# apple-idun.net
KiCad netlist of a schematic drawn in EAGLE
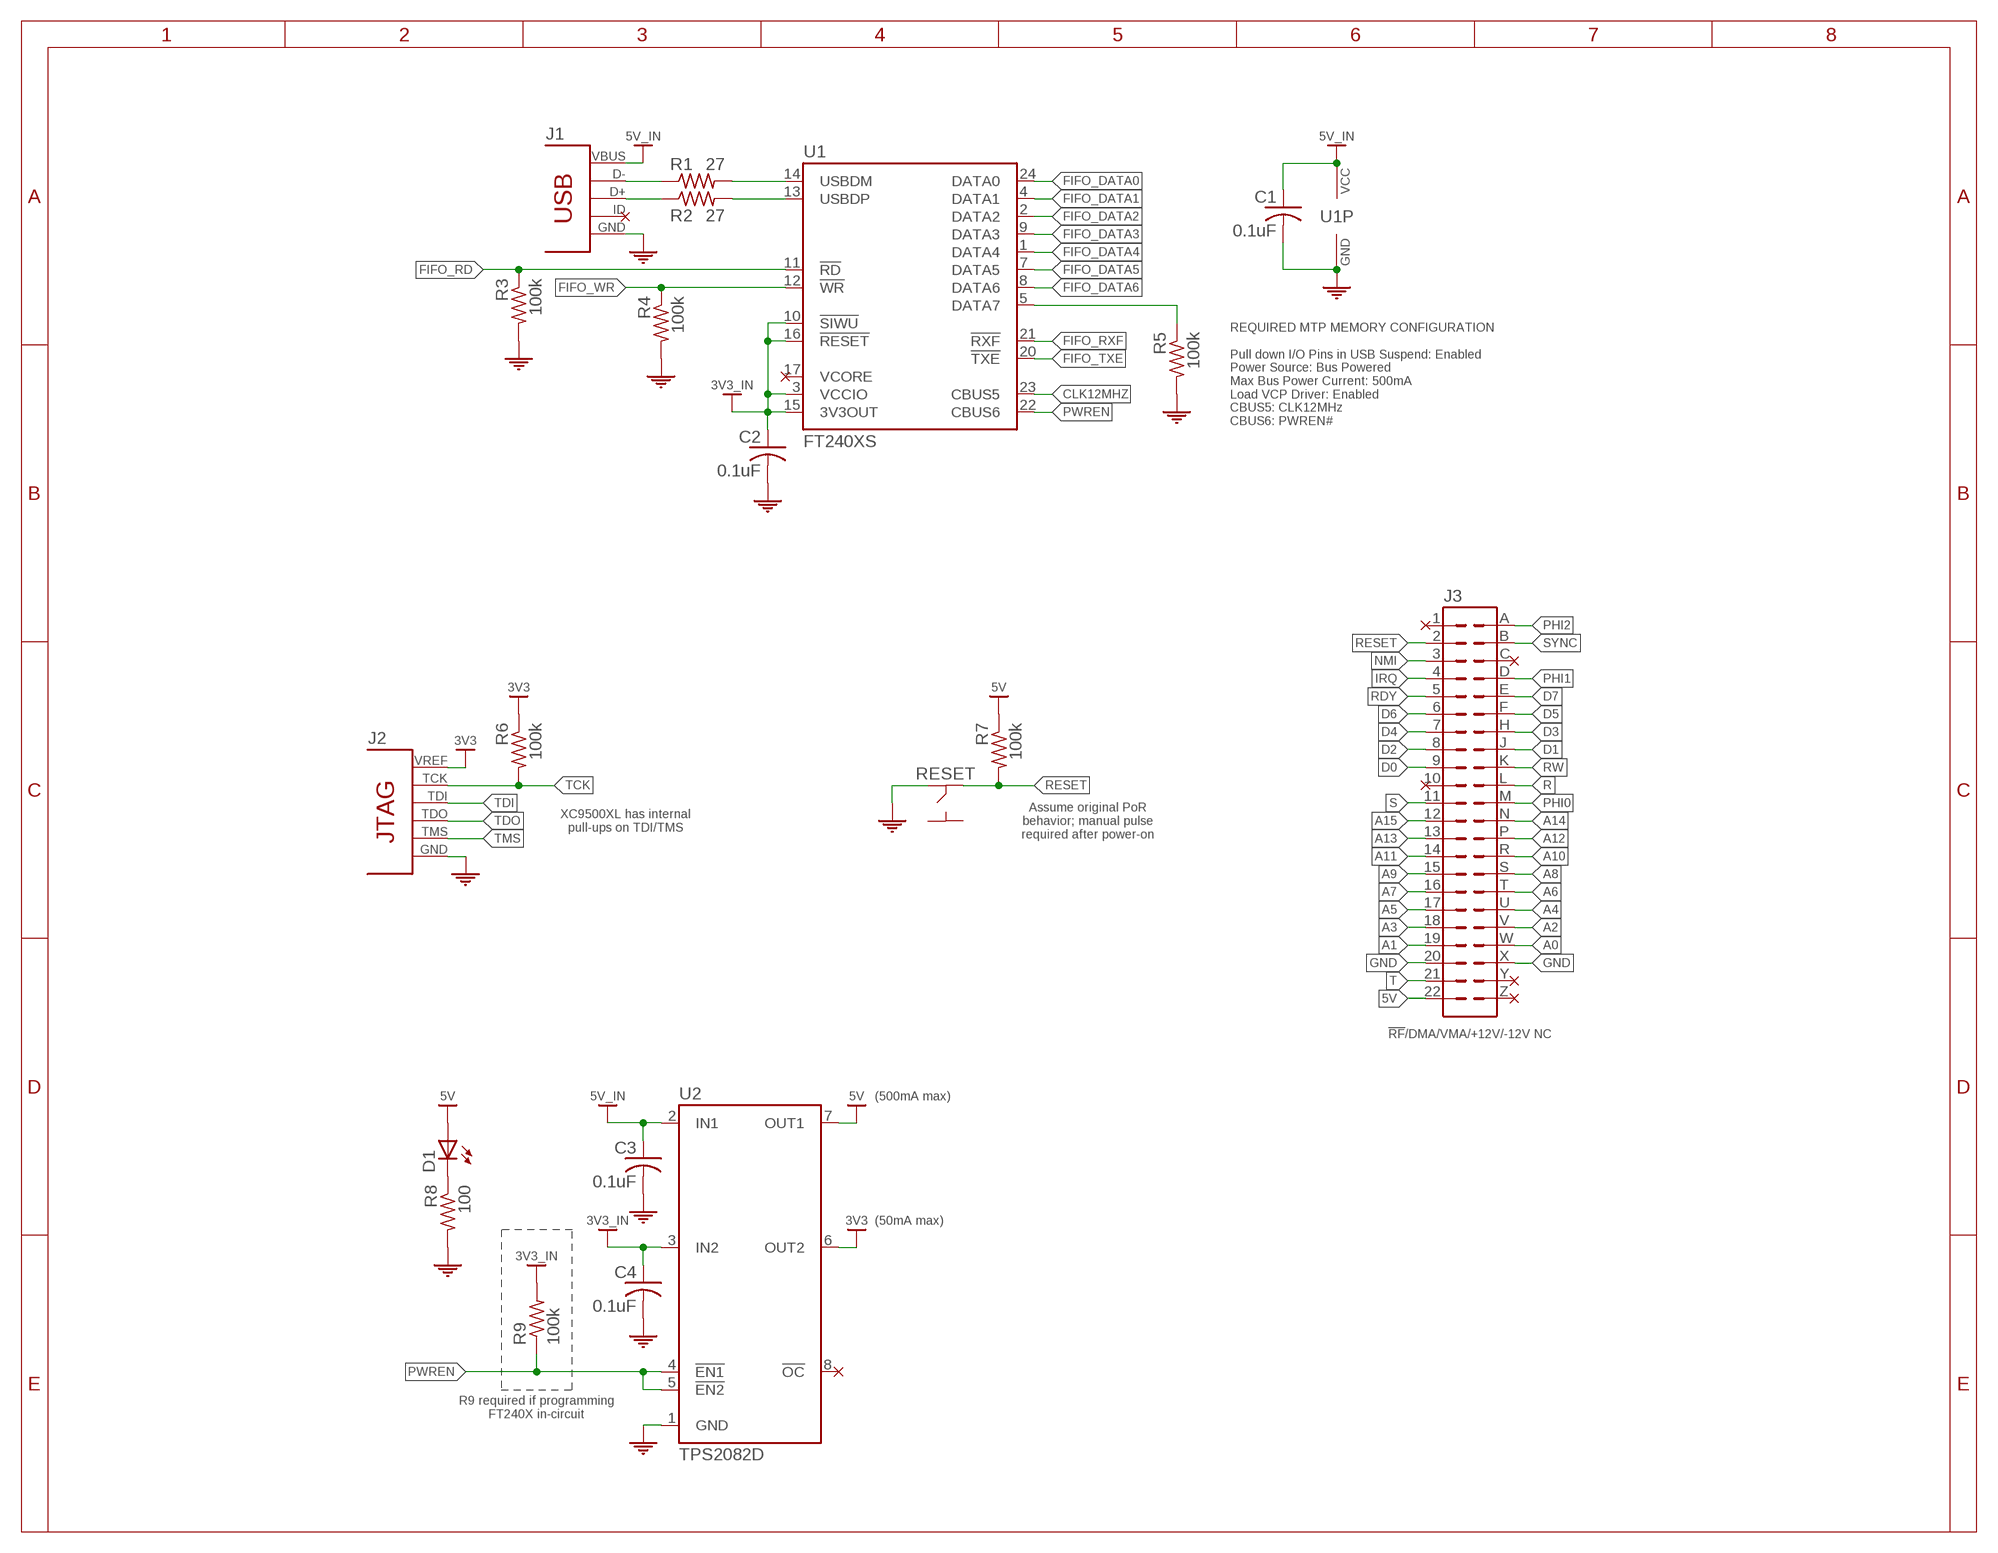
[diagram p0: schematic, sheet 1]
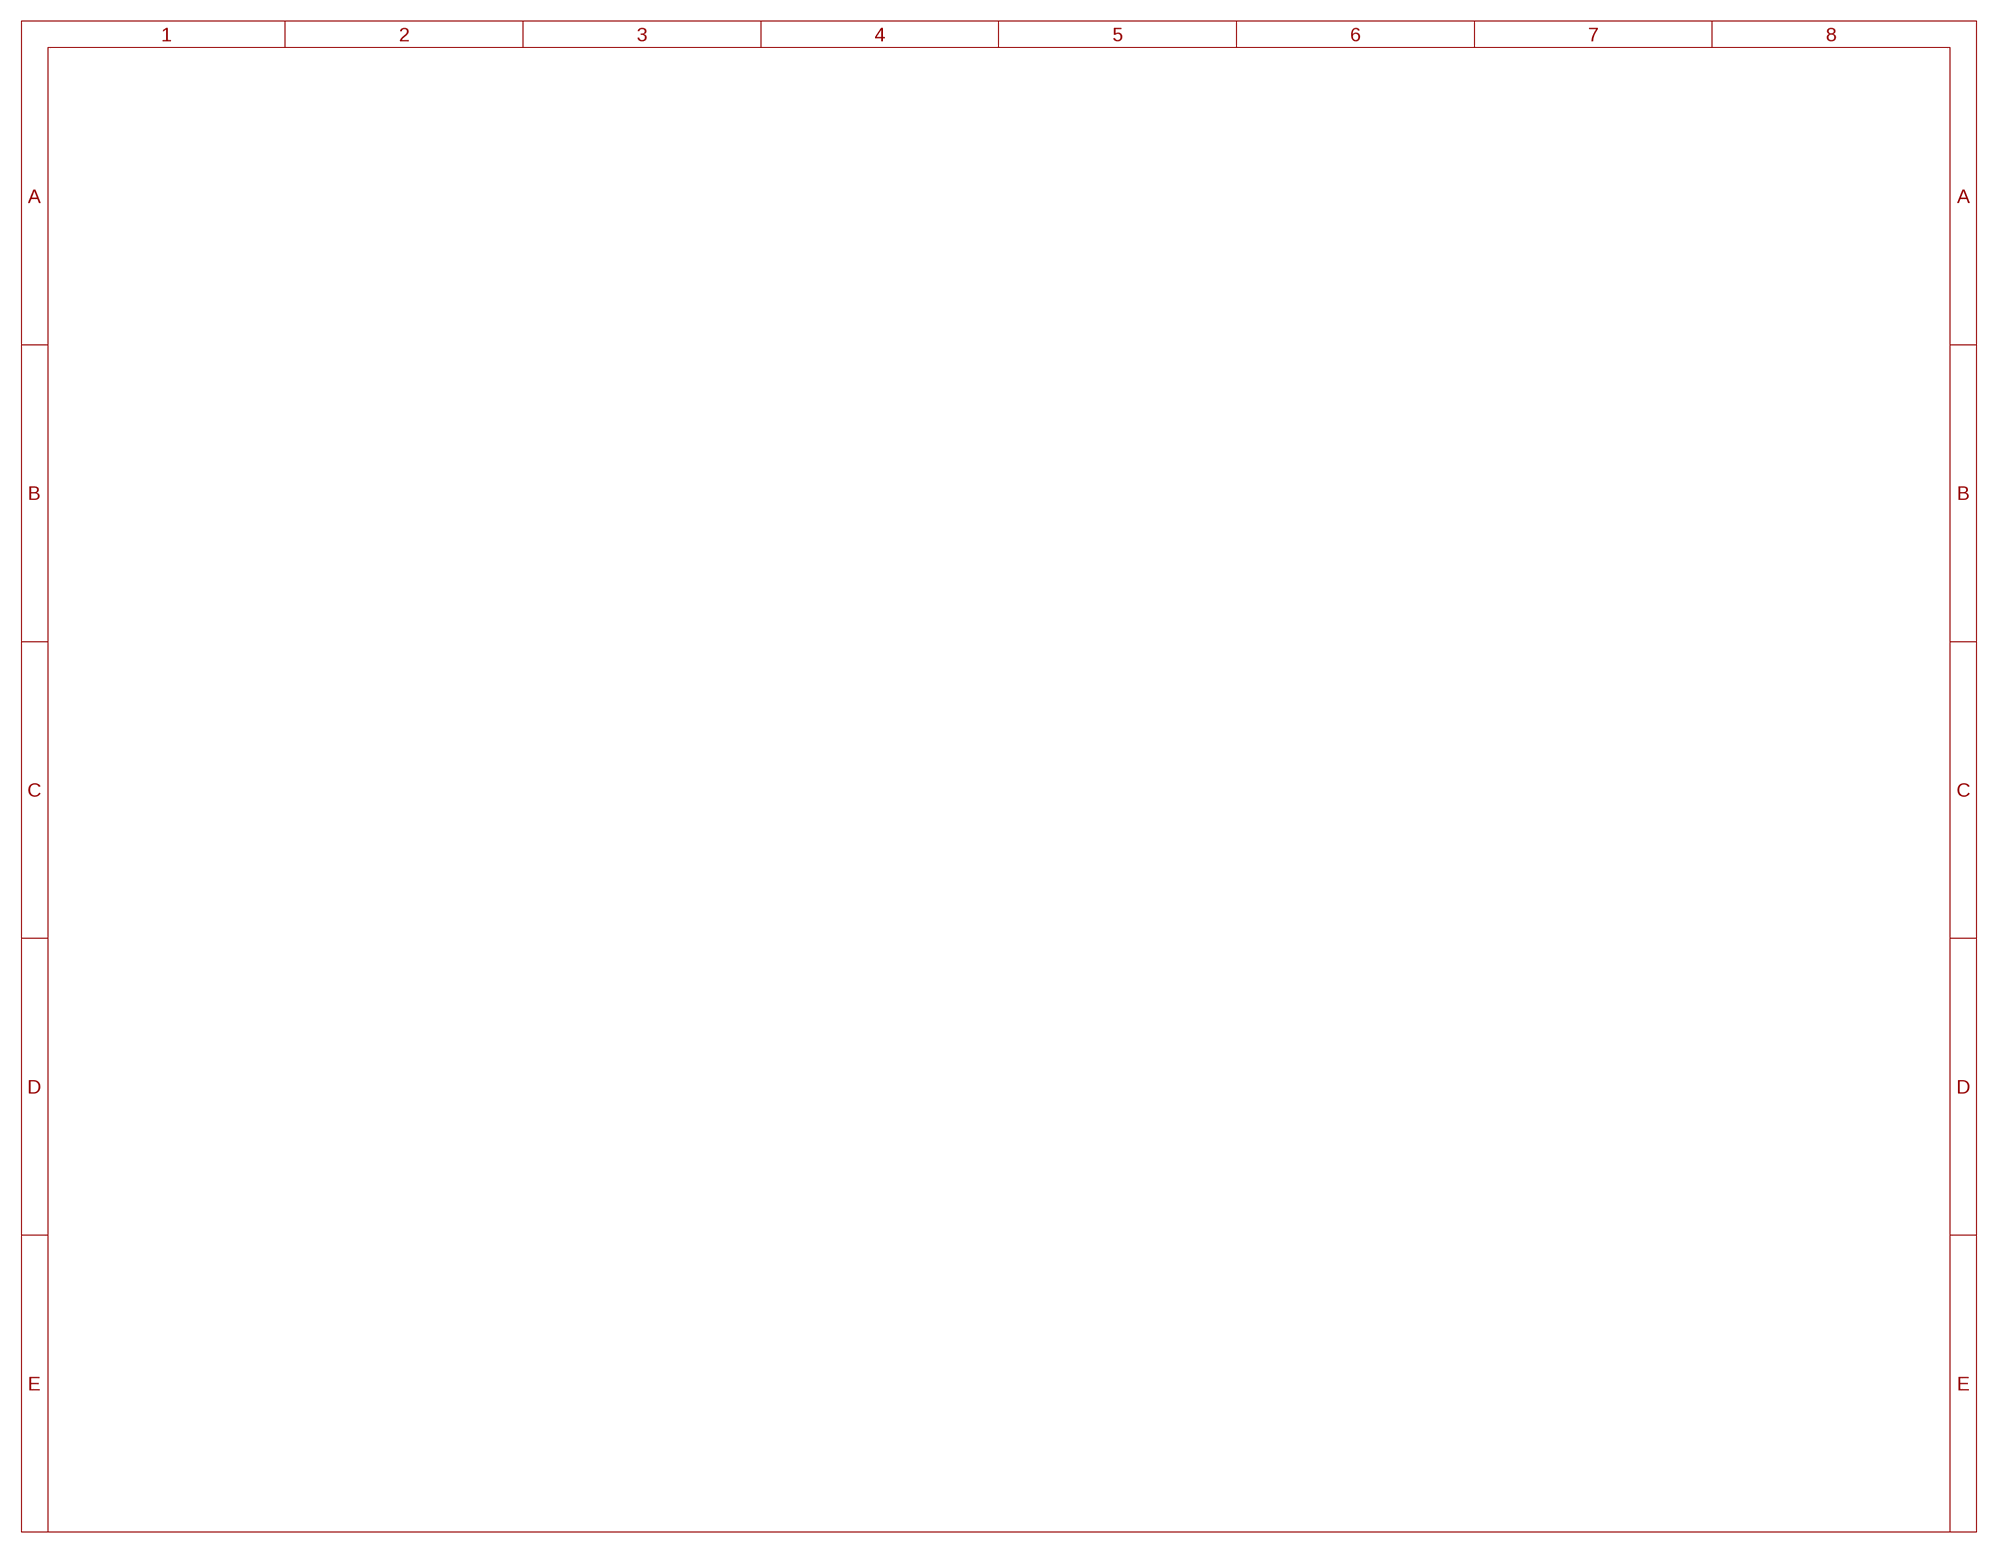
[diagram p1: schematic, sheet 2]

(export (version "E")
  (design (tool "Eeschema 10.0.6"))
  (components
    (comp (ref "C1")
      (value "0.1uF")
      (footprint "eagle-import:C0805")
      (libsource (lib "eagle-import") (part "C-USC0805"))
    )
    (comp (ref "C2")
      (value "0.1uF")
      (footprint "eagle-import:C0805")
      (libsource (lib "eagle-import") (part "C-USC0805"))
    )
    (comp (ref "C3")
      (value "0.1uF")
      (footprint "eagle-import:C0805")
      (libsource (lib "eagle-import") (part "C-USC0805"))
    )
    (comp (ref "C4")
      (value "0.1uF")
      (footprint "eagle-import:C0805")
      (libsource (lib "eagle-import") (part "C-USC0805"))
    )
    (comp (ref "D1")
      (value "LEDCHIP-LED0805")
      (footprint "eagle-import:CHIP-LED0805")
      (libsource (lib "eagle-import") (part "LEDCHIP-LED0805"))
    )
    (comp (ref "J1")
      (value "USBMICROB")
      (footprint "eagle-import:USBMICROB")
      (libsource (lib "eagle-import") (part "USBMICROB"))
    )
    (comp (ref "J2")
      (value "JTAG")
      (footprint "eagle-import:JTAG")
      (libsource (lib "eagle-import") (part "JTAG"))
    )
    (comp (ref "J3")
      (value "CON2X22")
      (footprint "eagle-import:CON2X22")
      (libsource (lib "eagle-import") (part "CON2X22"))
    )
    (comp (ref "R1")
      (value "27")
      (footprint "eagle-import:R0805")
      (libsource (lib "eagle-import") (part "R-US_R0805"))
    )
    (comp (ref "R2")
      (value "27")
      (footprint "eagle-import:R0805")
      (libsource (lib "eagle-import") (part "R-US_R0805"))
    )
    (comp (ref "R3")
      (value "100k")
      (footprint "eagle-import:R0805")
      (libsource (lib "eagle-import") (part "R-US_R0805"))
    )
    (comp (ref "R4")
      (value "100k")
      (footprint "eagle-import:R0805")
      (libsource (lib "eagle-import") (part "R-US_R0805"))
    )
    (comp (ref "R5")
      (value "100k")
      (footprint "eagle-import:R0805")
      (libsource (lib "eagle-import") (part "R-US_R0805"))
    )
    (comp (ref "R6")
      (value "100k")
      (footprint "eagle-import:R0805")
      (libsource (lib "eagle-import") (part "R-US_R0805"))
    )
    (comp (ref "R7")
      (value "100k")
      (footprint "eagle-import:R0805")
      (libsource (lib "eagle-import") (part "R-US_R0805"))
    )
    (comp (ref "R8")
      (value "100")
      (footprint "eagle-import:R0805")
      (libsource (lib "eagle-import") (part "R-US_R0805"))
    )
    (comp (ref "R9")
      (value "100k")
      (footprint "eagle-import:R0805")
      (libsource (lib "eagle-import") (part "R-US_R0805"))
    )
    (comp (ref "RESET")
      (value "TACTSW")
      (footprint "eagle-import:TACTSW")
      (libsource (lib "eagle-import") (part "TACTSW"))
    )
    (comp (ref "U1")
      (value "FT240XS")
      (footprint "eagle-import:SSOP24")
      (libsource (lib "eagle-import") (part "FT240XS"))
    )
    (comp (ref "U2")
      (value "TPS2082D")
      (footprint "eagle-import:SOIC8")
      (libsource (lib "eagle-import") (part "TPS2082D"))
    )
  )
  (nets
    (net (code "1") (name "3V3") (class "Default")
      (node (ref "J2") (pin "VREF") (pinfunction "VREF_VREF") (pintype "power_in"))
      (node (ref "R6") (pin "1") (pinfunction "1_1") (pintype "passive"))
      (node (ref "U2") (pin "6") (pinfunction "OUT2_6") (pintype "output"))
    )
    (net (code "2") (name "3V3_IN") (class "Default")
      (node (ref "C2") (pin "1") (pinfunction "1_1") (pintype "passive"))
      (node (ref "C4") (pin "1") (pinfunction "1_1") (pintype "passive"))
      (node (ref "R9") (pin "2") (pinfunction "2_2") (pintype "passive"))
      (node (ref "U1") (pin "10") (pinfunction "~{SIWU}_10") (pintype "input"))
      (node (ref "U1") (pin "15") (pinfunction "3V3OUT_15") (pintype "power_in"))
      (node (ref "U1") (pin "16") (pinfunction "~{RESET}_16") (pintype "input"))
      (node (ref "U1") (pin "3") (pinfunction "VCCIO_3") (pintype "power_in"))
      (node (ref "U2") (pin "3") (pinfunction "IN2_3") (pintype "input"))
    )
    (net (code "3") (name "5V") (class "Default")
      (node (ref "D1") (pin "A") (pinfunction "A_A") (pintype "passive"))
      (node (ref "J3") (pin "22") (pinfunction "22_22") (pintype "passive"))
      (node (ref "R7") (pin "1") (pinfunction "1_1") (pintype "passive"))
      (node (ref "U2") (pin "7") (pinfunction "OUT1_7") (pintype "output"))
    )
    (net (code "4") (name "5V_IN") (class "Default")
      (node (ref "C1") (pin "1") (pinfunction "1_1") (pintype "passive"))
      (node (ref "C3") (pin "1") (pinfunction "1_1") (pintype "passive"))
      (node (ref "J1") (pin "1") (pinfunction "1_1") (pintype "power_in"))
      (node (ref "U1") (pin "18") (pinfunction "VCC_18") (pintype "power_in"))
      (node (ref "U2") (pin "2") (pinfunction "IN1_2") (pintype "input"))
    )
    (net (code "5") (name "A0") (class "Default")
      (node (ref "J3") (pin "W") (pinfunction "W_W") (pintype "passive"))
    )
    (net (code "6") (name "A1") (class "Default")
      (node (ref "J3") (pin "19") (pinfunction "19_19") (pintype "passive"))
    )
    (net (code "7") (name "A2") (class "Default")
      (node (ref "J3") (pin "V") (pinfunction "V_V") (pintype "passive"))
    )
    (net (code "8") (name "A3") (class "Default")
      (node (ref "J3") (pin "18") (pinfunction "18_18") (pintype "passive"))
    )
    (net (code "9") (name "A4") (class "Default")
      (node (ref "J3") (pin "U") (pinfunction "U_U") (pintype "passive"))
    )
    (net (code "10") (name "A5") (class "Default")
      (node (ref "J3") (pin "17") (pinfunction "17_17") (pintype "passive"))
    )
    (net (code "11") (name "A6") (class "Default")
      (node (ref "J3") (pin "T") (pinfunction "T_T") (pintype "passive"))
    )
    (net (code "12") (name "A7") (class "Default")
      (node (ref "J3") (pin "16") (pinfunction "16_16") (pintype "passive"))
    )
    (net (code "13") (name "A8") (class "Default")
      (node (ref "J3") (pin "S") (pinfunction "S_S") (pintype "passive"))
    )
    (net (code "14") (name "A9") (class "Default")
      (node (ref "J3") (pin "15") (pinfunction "15_15") (pintype "passive"))
    )
    (net (code "15") (name "A10") (class "Default")
      (node (ref "J3") (pin "R") (pinfunction "R_R") (pintype "passive"))
    )
    (net (code "16") (name "A11") (class "Default")
      (node (ref "J3") (pin "14") (pinfunction "14_14") (pintype "passive"))
    )
    (net (code "17") (name "A12") (class "Default")
      (node (ref "J3") (pin "P") (pinfunction "P_P") (pintype "passive"))
    )
    (net (code "18") (name "A13") (class "Default")
      (node (ref "J3") (pin "13") (pinfunction "13_13") (pintype "passive"))
    )
    (net (code "19") (name "A14") (class "Default")
      (node (ref "J3") (pin "N") (pinfunction "N_N") (pintype "passive"))
    )
    (net (code "20") (name "A15") (class "Default")
      (node (ref "J3") (pin "12") (pinfunction "12_12") (pintype "passive"))
    )
    (net (code "21") (name "CLK12MHZ") (class "Default")
      (node (ref "U1") (pin "23") (pinfunction "CBUS5_23") (pintype "bidirectional"))
    )
    (net (code "22") (name "D0") (class "Default")
      (node (ref "J3") (pin "9") (pinfunction "9_9") (pintype "passive"))
    )
    (net (code "23") (name "D1") (class "Default")
      (node (ref "J3") (pin "J") (pinfunction "J_J") (pintype "passive"))
    )
    (net (code "24") (name "D2") (class "Default")
      (node (ref "J3") (pin "8") (pinfunction "8_8") (pintype "passive"))
    )
    (net (code "25") (name "D3") (class "Default")
      (node (ref "J3") (pin "H") (pinfunction "H_H") (pintype "passive"))
    )
    (net (code "26") (name "D4") (class "Default")
      (node (ref "J3") (pin "7") (pinfunction "7_7") (pintype "passive"))
    )
    (net (code "27") (name "D5") (class "Default")
      (node (ref "J3") (pin "F") (pinfunction "F_F") (pintype "passive"))
    )
    (net (code "28") (name "D6") (class "Default")
      (node (ref "J3") (pin "6") (pinfunction "6_6") (pintype "passive"))
    )
    (net (code "29") (name "D7") (class "Default")
      (node (ref "J3") (pin "E") (pinfunction "E_E") (pintype "passive"))
    )
    (net (code "30") (name "FIFO_DATA0") (class "Default")
      (node (ref "U1") (pin "24") (pinfunction "DATA0_24") (pintype "bidirectional"))
    )
    (net (code "31") (name "FIFO_DATA1") (class "Default")
      (node (ref "U1") (pin "4") (pinfunction "DATA1_4") (pintype "bidirectional"))
    )
    (net (code "32") (name "FIFO_DATA2") (class "Default")
      (node (ref "U1") (pin "2") (pinfunction "DATA2_2") (pintype "bidirectional"))
    )
    (net (code "33") (name "FIFO_DATA3") (class "Default")
      (node (ref "U1") (pin "9") (pinfunction "DATA3_9") (pintype "bidirectional"))
    )
    (net (code "34") (name "FIFO_DATA4") (class "Default")
      (node (ref "U1") (pin "1") (pinfunction "DATA4_1") (pintype "bidirectional"))
    )
    (net (code "35") (name "FIFO_DATA5") (class "Default")
      (node (ref "U1") (pin "7") (pinfunction "DATA5_7") (pintype "bidirectional"))
    )
    (net (code "36") (name "FIFO_DATA6") (class "Default")
      (node (ref "U1") (pin "8") (pinfunction "DATA6_8") (pintype "bidirectional"))
    )
    (net (code "37") (name "FIFO_RD") (class "Default")
      (node (ref "R3") (pin "1") (pinfunction "1_1") (pintype "passive"))
      (node (ref "U1") (pin "11") (pinfunction "~{RD}_11") (pintype "input"))
    )
    (net (code "38") (name "FIFO_RXF") (class "Default")
      (node (ref "U1") (pin "21") (pinfunction "~{RXF}_21") (pintype "output"))
    )
    (net (code "39") (name "FIFO_TXE") (class "Default")
      (node (ref "U1") (pin "20") (pinfunction "~{TXE}_20") (pintype "output"))
    )
    (net (code "40") (name "FIFO_WR") (class "Default")
      (node (ref "R4") (pin "1") (pinfunction "1_1") (pintype "passive"))
      (node (ref "U1") (pin "12") (pinfunction "~{WR}_12") (pintype "input"))
    )
    (net (code "41") (name "GND") (class "Default")
      (node (ref "C1") (pin "2") (pinfunction "2_2") (pintype "passive"))
      (node (ref "C2") (pin "2") (pinfunction "2_2") (pintype "passive"))
      (node (ref "C3") (pin "2") (pinfunction "2_2") (pintype "passive"))
      (node (ref "C4") (pin "2") (pinfunction "2_2") (pintype "passive"))
      (node (ref "J1") (pin "5") (pinfunction "5_5") (pintype "power_in"))
      (node (ref "J1") (pin "6") (pinfunction "5_6") (pintype "power_in"))
      (node (ref "J1") (pin "7") (pinfunction "5_7") (pintype "power_in"))
      (node (ref "J1") (pin "8") (pinfunction "5_8") (pintype "power_in"))
      (node (ref "J1") (pin "9") (pinfunction "5_9") (pintype "power_in"))
      (node (ref "J2") (pin "GND") (pinfunction "GND_GND") (pintype "power_in"))
      (node (ref "J3") (pin "20") (pinfunction "20_20") (pintype "passive"))
      (node (ref "J3") (pin "X") (pinfunction "X_X") (pintype "passive"))
      (node (ref "R3") (pin "2") (pinfunction "2_2") (pintype "passive"))
      (node (ref "R4") (pin "2") (pinfunction "2_2") (pintype "passive"))
      (node (ref "R5") (pin "2") (pinfunction "2_2") (pintype "passive"))
      (node (ref "R8") (pin "2") (pinfunction "2_2") (pintype "passive"))
      (node (ref "RESET") (pin "1") (pinfunction "1_1") (pintype "passive"))
      (node (ref "U1") (pin "19") (pinfunction "GND_19") (pintype "power_in"))
      (node (ref "U1") (pin "6") (pinfunction "GND_6") (pintype "power_in"))
      (node (ref "U2") (pin "1") (pinfunction "GND_1") (pintype "power_in"))
    )
    (net (code "42") (name "IRQ") (class "Default")
      (node (ref "J3") (pin "4") (pinfunction "4_4") (pintype "passive"))
    )
    (net (code "43") (name "NMI") (class "Default")
      (node (ref "J3") (pin "3") (pinfunction "3_3") (pintype "passive"))
    )
    (net (code "44") (name "Net-(D1-PadC)") (class "Default")
      (node (ref "D1") (pin "C") (pinfunction "C_C") (pintype "passive"))
      (node (ref "R8") (pin "1") (pinfunction "1_1") (pintype "passive"))
    )
    (net (code "45") (name "Net-(J1-Pad2)") (class "Default")
      (node (ref "J1") (pin "2") (pinfunction "2_2") (pintype "bidirectional"))
      (node (ref "R1") (pin "1") (pinfunction "1_1") (pintype "passive"))
    )
    (net (code "46") (name "Net-(J1-Pad3)") (class "Default")
      (node (ref "J1") (pin "3") (pinfunction "3_3") (pintype "bidirectional"))
      (node (ref "R2") (pin "1") (pinfunction "1_1") (pintype "passive"))
    )
    (net (code "47") (name "Net-(U1A-DATA7)") (class "Default")
      (node (ref "R5") (pin "1") (pinfunction "1_1") (pintype "passive"))
      (node (ref "U1") (pin "5") (pinfunction "DATA7_5") (pintype "bidirectional"))
    )
    (net (code "48") (name "Net-(U1A-USBDM)") (class "Default")
      (node (ref "R1") (pin "2") (pinfunction "2_2") (pintype "passive"))
      (node (ref "U1") (pin "14") (pinfunction "USBDM_14") (pintype "input"))
    )
    (net (code "49") (name "Net-(U1A-USBDP)") (class "Default")
      (node (ref "R2") (pin "2") (pinfunction "2_2") (pintype "passive"))
      (node (ref "U1") (pin "13") (pinfunction "USBDP_13") (pintype "input"))
    )
    (net (code "50") (name "PHI0") (class "Default")
      (node (ref "J3") (pin "M") (pinfunction "M_M") (pintype "passive"))
    )
    (net (code "51") (name "PHI1") (class "Default")
      (node (ref "J3") (pin "D") (pinfunction "D_D") (pintype "passive"))
    )
    (net (code "52") (name "PHI2") (class "Default")
      (node (ref "J3") (pin "A") (pinfunction "A_A") (pintype "passive"))
    )
    (net (code "53") (name "PWREN") (class "Default")
      (node (ref "R9") (pin "1") (pinfunction "1_1") (pintype "passive"))
      (node (ref "U1") (pin "22") (pinfunction "CBUS6_22") (pintype "bidirectional"))
      (node (ref "U2") (pin "4") (pinfunction "~{EN1}_4") (pintype "input"))
      (node (ref "U2") (pin "5") (pinfunction "~{EN2}_5") (pintype "input"))
    )
    (net (code "54") (name "R") (class "Default")
      (node (ref "J3") (pin "L") (pinfunction "L_L") (pintype "passive"))
    )
    (net (code "55") (name "RDY") (class "Default")
      (node (ref "J3") (pin "5") (pinfunction "5_5") (pintype "passive"))
    )
    (net (code "56") (name "RESET") (class "Default")
      (node (ref "J3") (pin "2") (pinfunction "2_2") (pintype "passive"))
      (node (ref "R7") (pin "2") (pinfunction "2_2") (pintype "passive"))
      (node (ref "RESET") (pin "2") (pinfunction "2_2") (pintype "passive"))
    )
    (net (code "57") (name "RW") (class "Default")
      (node (ref "J3") (pin "K") (pinfunction "K_K") (pintype "passive"))
    )
    (net (code "58") (name "S") (class "Default")
      (node (ref "J3") (pin "11") (pinfunction "11_11") (pintype "passive"))
    )
    (net (code "59") (name "SYNC") (class "Default")
      (node (ref "J3") (pin "B") (pinfunction "B_B") (pintype "passive"))
    )
    (net (code "60") (name "T") (class "Default")
      (node (ref "J3") (pin "21") (pinfunction "21_21") (pintype "passive"))
    )
    (net (code "61") (name "TCK") (class "Default")
      (node (ref "J2") (pin "TCK") (pinfunction "TCK_TCK") (pintype "input"))
      (node (ref "R6") (pin "2") (pinfunction "2_2") (pintype "passive"))
    )
    (net (code "62") (name "TDI") (class "Default")
      (node (ref "J2") (pin "TDI") (pinfunction "TDI_TDI") (pintype "input"))
    )
    (net (code "63") (name "TDO") (class "Default")
      (node (ref "J2") (pin "TDO") (pinfunction "TDO_TDO") (pintype "output"))
    )
    (net (code "64") (name "TMS") (class "Default")
      (node (ref "J2") (pin "TMS") (pinfunction "TMS_TMS") (pintype "input"))
    )
    (net (code "65") (name "VCORE") (class "Default")
      (node (ref "U1") (pin "17") (pinfunction "VCORE_17") (pintype "power_in"))
    )
    (net (code "66") (name "unconnected-(J1-Pad4)") (class "Default")
      (node (ref "J1") (pin "4") (pinfunction "4_4") (pintype "passive"))
    )
    (net (code "67") (name "unconnected-(J3-Pad1)") (class "Default")
      (node (ref "J3") (pin "1") (pinfunction "1_1") (pintype "passive"))
    )
    (net (code "68") (name "unconnected-(J3-Pad10)") (class "Default")
      (node (ref "J3") (pin "10") (pinfunction "10_10") (pintype "passive"))
    )
    (net (code "69") (name "unconnected-(J3-PadC)") (class "Default")
      (node (ref "J3") (pin "C") (pinfunction "C_C") (pintype "passive"))
    )
    (net (code "70") (name "unconnected-(J3-PadY)") (class "Default")
      (node (ref "J3") (pin "Y") (pinfunction "Y_Y") (pintype "passive"))
    )
    (net (code "71") (name "unconnected-(J3-PadZ)") (class "Default")
      (node (ref "J3") (pin "Z") (pinfunction "Z_Z") (pintype "passive"))
    )
    (net (code "72") (name "unconnected-(RESET-Pad3)") (class "Default")
      (node (ref "RESET") (pin "3") (pinfunction "3_3") (pintype "passive"))
    )
    (net (code "73") (name "unconnected-(RESET-Pad4)") (class "Default")
      (node (ref "RESET") (pin "4") (pinfunction "4_4") (pintype "passive"))
    )
    (net (code "74") (name "unconnected-(U2-~{OC}-Pad8)") (class "Default")
      (node (ref "U2") (pin "8") (pinfunction "~{OC}_8") (pintype "output"))
    )
  )
)
